# KD055HDFIA001-C001A-_5_5_Inch_MIPI_Radxa.net
KiCad netlist of a schematic drawn in EAGLE
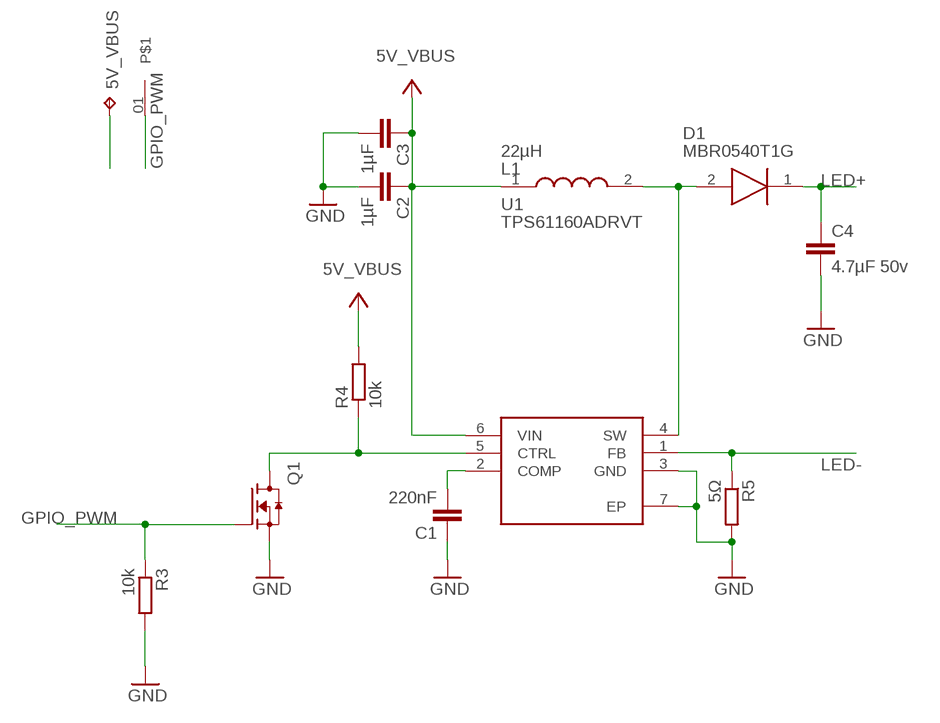
[diagram p0: schematic, sheet 1]
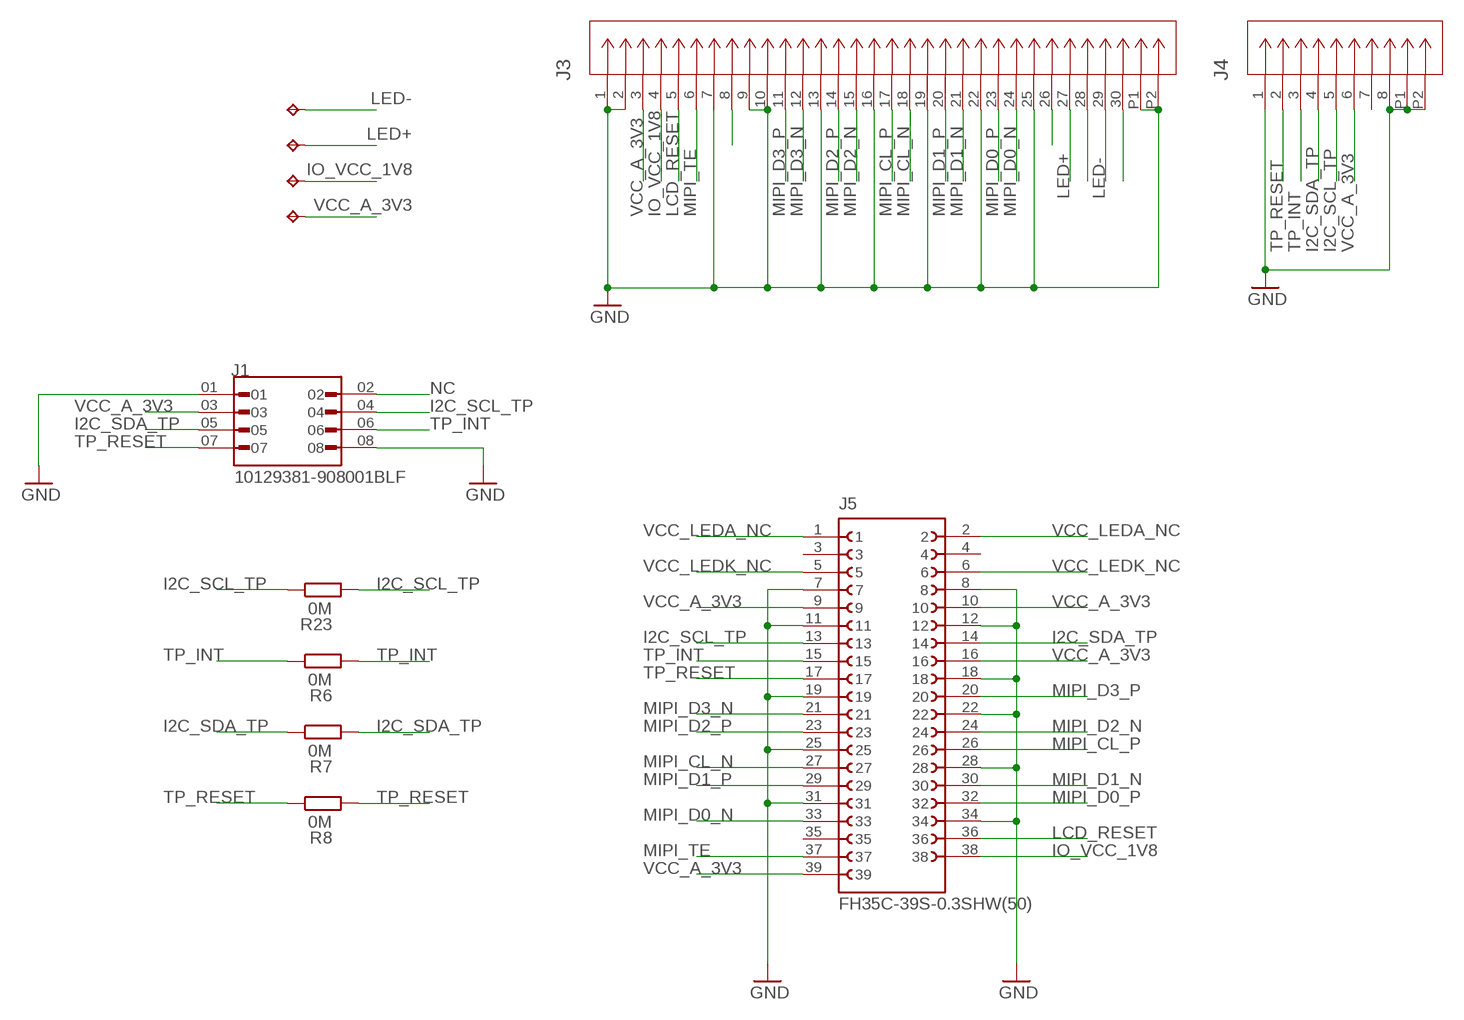
[diagram p1: schematic, sheet 2]
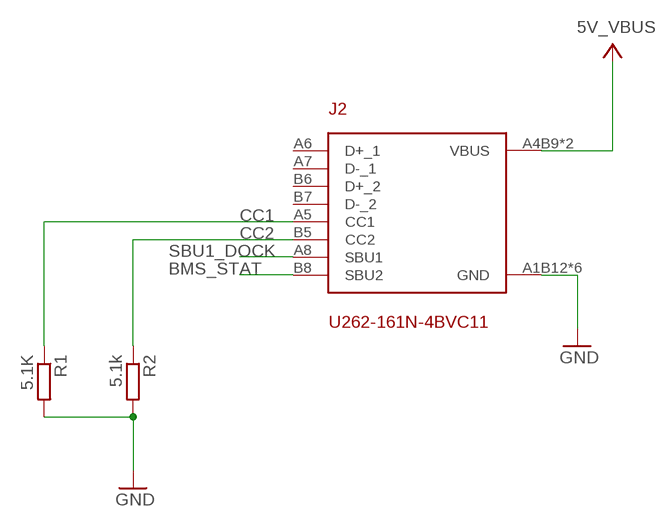
[diagram p2: schematic, sheet 3]

(export (version "E")
  (design (tool "Eeschema 10.0.6"))
  (components
    (comp (ref "5V_VBUS")
      (value "TPTP19R")
      (footprint "eagle-import:TP19R")
      (libsource (lib "eagle-import") (part "TPTP19R"))
    )
    (comp (ref "C1")
      (value "220nF")
      (footprint "eagle-import:C0603")
      (libsource (lib "eagle-import") (part "C-EUC0603"))
    )
    (comp (ref "C2")
      (value "1µF")
      (footprint "eagle-import:C0603")
      (libsource (lib "eagle-import") (part "C-EUC0603"))
    )
    (comp (ref "C3")
      (value "1µF")
      (footprint "eagle-import:C0603")
      (libsource (lib "eagle-import") (part "C-EUC0603"))
    )
    (comp (ref "C4")
      (value "4.7µF 50v")
      (footprint "eagle-import:C0805")
      (libsource (lib "eagle-import") (part "C-EUC0805"))
    )
    (comp (ref "D1")
      (value "MBR0540T1G")
      (footprint "eagle-import:SOD3716X135N")
      (fields (field (name "MOUSER_PART_NUMBER") "863-MBR0540T1G") (field (name "RS_PART_NUMBER") "0463842P"))
      (libsource (lib "eagle-import") (part "MBR0540T1G"))
    )
    (comp (ref "L1")
      (value "22µH")
      (footprint "eagle-import:VLCF4020_1")
      (fields
        (field (name "MANUFACTURER_PART_NUMBER") "VLCF4020T-220MR56")
        (field (name "MOUSER_PART_NUMBER") "810-VLCF4020T220MR56")
        (field (name "RS_PART_NUMBER") "6442781")
      )
      (libsource (lib "eagle-import") (part "VLCF4020T-220MR56"))
    )
    (comp (ref "Q1")
      (value "AO3400A")
      (footprint "eagle-import:SOT95P280X125-3N")
      (fields (field (name "DIGI-KEY_PART_NUMBER") "785-1000-1-ND") (field (name "MF") "Alpha &"))
      (libsource (lib "eagle-import") (part "AO3400A"))
    )
    (comp (ref "R3")
      (value "10k")
      (footprint "eagle-import:R0603")
      (libsource (lib "eagle-import") (part "rcl_334_R-EU_R0603"))
    )
    (comp (ref "R4")
      (value "10k")
      (footprint "eagle-import:R0603")
      (libsource (lib "eagle-import") (part "rcl_334_R-EU_R0603"))
    )
    (comp (ref "R5")
      (value "5Ω")
      (footprint "eagle-import:R0603")
      (libsource (lib "eagle-import") (part "rcl_334_R-EU_R0603"))
    )
    (comp (ref "U$1")
      (value "PAD")
      (footprint "eagle-import:AMPHENOL_10129381-908001BLF")
      (libsource (lib "eagle-import") (part "PAD"))
    )
    (comp (ref "U1")
      (value "TPS61160ADRVT")
      (footprint "eagle-import:SON65P200X200X80-7N")
      (fields
        (field (name "MOUSER_PART_NUMBER") "595-TPS61160ADRVT")
        (field (name "RS_PART_NUMBER") "7099044P")
      )
      (libsource (lib "eagle-import") (part "TPS61160ADRVT"))
    )
    (comp (ref "J2")
      (value "U262-161N-4BVC11")
      (footprint "eagle-import:U262-161N-4BVC11")
      (libsource (lib "eagle-import") (part "U262-161N-4BVC11"))
    )
    (comp (ref "R1")
      (value "5.1K")
      (footprint "eagle-import:R0603")
      (libsource (lib "eagle-import") (part "rcl_334_R-EU_R0603"))
    )
    (comp (ref "R2")
      (value "5.1k")
      (footprint "eagle-import:R0603")
      (libsource (lib "eagle-import") (part "rcl_334_R-EU_R0603"))
    )
    (comp (ref "IO_VCC_1V8")
      (value "TPTP19R")
      (footprint "eagle-import:TP19R")
      (libsource (lib "eagle-import") (part "TPTP19R"))
    )
    (comp (ref "J1")
      (value "10129381-908001BLF")
      (footprint "eagle-import:AMPHENOL_10129381-908001BLF")
      (fields (field (name "MANUFACTURER") "Amphenol ICC"))
      (libsource (lib "eagle-import") (part "10129381-908001BLF"))
    )
    (comp (ref "J3")
      (value "5051103091")
      (footprint "eagle-import:CON_5051103091_MOL")
      (fields (field (name "COPYRIGHT") "Copyright (C) 2023 Ultra Librarian. All rights reserved."))
      (libsource (lib "eagle-import") (part "5051103091"))
    )
    (comp (ref "J4")
      (value "5051100892")
      (footprint "eagle-import:CON_5051100892_MOL")
      (fields (field (name "COPYRIGHT") "Copyright (C) 2023 Ultra Librarian. All rights reserved."))
      (libsource (lib "eagle-import") (part "5051100892"))
    )
    (comp (ref "J5")
      (value "FH35C-39S-0.3SHW(50)")
      (footprint "eagle-import:HRS_FH35C-39S-0.3SHW(50)")
      (fields (field (name "MF") "Hirose Electric"))
      (libsource (lib "eagle-import") (part "FH35C-39S-0.3SHW(50)"))
    )
    (comp (ref "LED+")
      (value "TPTP19R")
      (footprint "eagle-import:TP19R")
      (libsource (lib "eagle-import") (part "TPTP19R"))
    )
    (comp (ref "LED-")
      (value "TPTP19R")
      (footprint "eagle-import:TP19R")
      (libsource (lib "eagle-import") (part "TPTP19R"))
    )
    (comp (ref "R6")
      (value "0M")
      (footprint "eagle-import:R0402")
      (libsource (lib "eagle-import") (part "R-EU_R0402"))
    )
    (comp (ref "R7")
      (value "0M")
      (footprint "eagle-import:R0402")
      (libsource (lib "eagle-import") (part "R-EU_R0402"))
    )
    (comp (ref "R8")
      (value "0M")
      (footprint "eagle-import:R0402")
      (libsource (lib "eagle-import") (part "R-EU_R0402"))
    )
    (comp (ref "R23")
      (value "0M")
      (footprint "eagle-import:R0402")
      (libsource (lib "eagle-import") (part "R-EU_R0402"))
    )
    (comp (ref "VCC_A_3V3")
      (value "TPTP19R")
      (footprint "eagle-import:TP19R")
      (libsource (lib "eagle-import") (part "TPTP19R"))
    )
  )
  (nets
    (net (code "1") (name "5V_VBUS") (class "Default")
      (node (ref "5V_VBUS") (pin "TP") (pinfunction "TP_TP") (pintype "input"))
      (node (ref "C2") (pin "1") (pinfunction "1_1") (pintype "passive"))
      (node (ref "C3") (pin "1") (pinfunction "1_1") (pintype "passive"))
      (node (ref "J2") (pin "A4B9") (pinfunction "VBUS_A4B9") (pintype "bidirectional"))
      (node (ref "J2") (pin "B4A9") (pinfunction "VBUS_B4A9") (pintype "bidirectional"))
      (node (ref "L1") (pin "1") (pinfunction "1_1") (pintype "bidirectional"))
      (node (ref "R4") (pin "2") (pinfunction "2_2") (pintype "passive"))
      (node (ref "U1") (pin "6") (pinfunction "VIN_6") (pintype "input"))
    )
    (net (code "2") (name "BMS_STAT") (class "Default")
      (node (ref "J2") (pin "B8") (pinfunction "SBU2_B8") (pintype "bidirectional"))
    )
    (net (code "3") (name "CC1") (class "Default")
      (node (ref "J2") (pin "A5") (pinfunction "CC1_A5") (pintype "bidirectional"))
      (node (ref "R1") (pin "1") (pinfunction "1_1") (pintype "passive"))
    )
    (net (code "4") (name "CC2") (class "Default")
      (node (ref "J2") (pin "B5") (pinfunction "CC2_B5") (pintype "bidirectional"))
      (node (ref "R2") (pin "1") (pinfunction "1_1") (pintype "passive"))
    )
    (net (code "5") (name "GND") (class "Default")
      (node (ref "C1") (pin "1") (pinfunction "1_1") (pintype "passive"))
      (node (ref "C2") (pin "2") (pinfunction "2_2") (pintype "passive"))
      (node (ref "C3") (pin "2") (pinfunction "2_2") (pintype "passive"))
      (node (ref "C4") (pin "2") (pinfunction "2_2") (pintype "passive"))
      (node (ref "J1") (pin "01") (pinfunction "01_01") (pintype "passive"))
      (node (ref "J1") (pin "08") (pinfunction "08_08") (pintype "passive"))
      (node (ref "J2") (pin "A1B12") (pinfunction "GND_A1B12") (pintype "bidirectional"))
      (node (ref "J2") (pin "B1A12") (pinfunction "GND_B1A12") (pintype "bidirectional"))
      (node (ref "J2") (pin "SHIELD_1") (pinfunction "GND_SHIELD_1") (pintype "bidirectional"))
      (node (ref "J2") (pin "SHIELD_2") (pinfunction "GND_SHIELD_2") (pintype "bidirectional"))
      (node (ref "J2") (pin "SHIELD_3") (pinfunction "GND_SHIELD_3") (pintype "bidirectional"))
      (node (ref "J2") (pin "SHIELD_4") (pinfunction "GND_SHIELD_4") (pintype "bidirectional"))
      (node (ref "J3") (pin "1") (pinfunction "1_1") (pintype "passive"))
      (node (ref "J3") (pin "10") (pinfunction "10_10") (pintype "passive"))
      (node (ref "J3") (pin "13") (pinfunction "13_13") (pintype "passive"))
      (node (ref "J3") (pin "16") (pinfunction "16_16") (pintype "passive"))
      (node (ref "J3") (pin "19") (pinfunction "19_19") (pintype "passive"))
      (node (ref "J3") (pin "2") (pinfunction "2_2") (pintype "passive"))
      (node (ref "J3") (pin "22") (pinfunction "22_22") (pintype "passive"))
      (node (ref "J3") (pin "25") (pinfunction "25_25") (pintype "passive"))
      (node (ref "J3") (pin "7") (pinfunction "7_7") (pintype "passive"))
      (node (ref "J3") (pin "9") (pinfunction "9_9") (pintype "passive"))
      (node (ref "J3") (pin "P1") (pinfunction "P1_P1") (pintype "passive"))
      (node (ref "J3") (pin "P2") (pinfunction "P2_P2") (pintype "passive"))
      (node (ref "J4") (pin "1") (pinfunction "1_1") (pintype "passive"))
      (node (ref "J4") (pin "8") (pinfunction "8_8") (pintype "passive"))
      (node (ref "J4") (pin "P1") (pinfunction "P1_P1") (pintype "passive"))
      (node (ref "J4") (pin "P2") (pinfunction "P2_P2") (pintype "passive"))
      (node (ref "J5") (pin "11") (pinfunction "11_11") (pintype "passive"))
      (node (ref "J5") (pin "12") (pinfunction "12_12") (pintype "passive"))
      (node (ref "J5") (pin "18") (pinfunction "18_18") (pintype "passive"))
      (node (ref "J5") (pin "19") (pinfunction "19_19") (pintype "passive"))
      (node (ref "J5") (pin "22") (pinfunction "22_22") (pintype "passive"))
      (node (ref "J5") (pin "25") (pinfunction "25_25") (pintype "passive"))
      (node (ref "J5") (pin "28") (pinfunction "28_28") (pintype "passive"))
      (node (ref "J5") (pin "31") (pinfunction "31_31") (pintype "passive"))
      (node (ref "J5") (pin "34") (pinfunction "34_34") (pintype "passive"))
      (node (ref "J5") (pin "7") (pinfunction "7_7") (pintype "passive"))
      (node (ref "J5") (pin "8") (pinfunction "8_8") (pintype "passive"))
      (node (ref "Q1") (pin "2") (pinfunction "S_2") (pintype "passive"))
      (node (ref "R1") (pin "2") (pinfunction "2_2") (pintype "passive"))
      (node (ref "R2") (pin "2") (pinfunction "2_2") (pintype "passive"))
      (node (ref "R3") (pin "2") (pinfunction "2_2") (pintype "passive"))
      (node (ref "R5") (pin "2") (pinfunction "2_2") (pintype "passive"))
      (node (ref "U1") (pin "3") (pinfunction "GND_3") (pintype "output"))
      (node (ref "U1") (pin "7") (pinfunction "EP_7") (pintype "power_in"))
    )
    (net (code "6") (name "GPIO_PWM") (class "Default")
      (node (ref "Q1") (pin "1") (pinfunction "G_1") (pintype "passive"))
      (node (ref "R3") (pin "1") (pinfunction "1_1") (pintype "passive"))
      (node (ref "U$1") (pin "01") (pinfunction "P$1_01") (pintype "bidirectional"))
    )
    (net (code "7") (name "I2C_SCL_TP") (class "Default")
      (node (ref "J1") (pin "04") (pinfunction "04_04") (pintype "passive"))
      (node (ref "J4") (pin "5") (pinfunction "5_5") (pintype "passive"))
      (node (ref "J5") (pin "13") (pinfunction "13_13") (pintype "passive"))
      (node (ref "R23") (pin "1") (pinfunction "1_1") (pintype "passive"))
      (node (ref "R23") (pin "2") (pinfunction "2_2") (pintype "passive"))
    )
    (net (code "8") (name "I2C_SDA_TP") (class "Default")
      (node (ref "J1") (pin "05") (pinfunction "05_05") (pintype "passive"))
      (node (ref "J4") (pin "4") (pinfunction "4_4") (pintype "passive"))
      (node (ref "J5") (pin "14") (pinfunction "14_14") (pintype "passive"))
      (node (ref "R7") (pin "1") (pinfunction "1_1") (pintype "passive"))
      (node (ref "R7") (pin "2") (pinfunction "2_2") (pintype "passive"))
    )
    (net (code "9") (name "IO_VCC_1V8") (class "Default")
      (node (ref "IO_VCC_1V8") (pin "TP") (pinfunction "TP_TP") (pintype "input"))
      (node (ref "J3") (pin "4") (pinfunction "4_4") (pintype "passive"))
      (node (ref "J5") (pin "38") (pinfunction "38_38") (pintype "passive"))
    )
    (net (code "10") (name "LCD_RESET") (class "Default")
      (node (ref "J3") (pin "5") (pinfunction "5_5") (pintype "passive"))
      (node (ref "J5") (pin "36") (pinfunction "36_36") (pintype "passive"))
    )
    (net (code "11") (name "LED+") (class "Default")
      (node (ref "C4") (pin "1") (pinfunction "1_1") (pintype "passive"))
      (node (ref "D1") (pin "1") (pinfunction "K_1") (pintype "bidirectional"))
      (node (ref "J3") (pin "27") (pinfunction "27_27") (pintype "passive"))
      (node (ref "LED+") (pin "TP") (pinfunction "TP_TP") (pintype "input"))
    )
    (net (code "12") (name "LED-") (class "Default")
      (node (ref "J3") (pin "29") (pinfunction "29_29") (pintype "passive"))
      (node (ref "LED-") (pin "TP") (pinfunction "TP_TP") (pintype "input"))
      (node (ref "R5") (pin "1") (pinfunction "1_1") (pintype "passive"))
      (node (ref "U1") (pin "1") (pinfunction "FB_1") (pintype "input"))
    )
    (net (code "13") (name "MIPI_CL_N") (class "Default")
      (node (ref "J3") (pin "18") (pinfunction "18_18") (pintype "passive"))
      (node (ref "J5") (pin "27") (pinfunction "27_27") (pintype "passive"))
    )
    (net (code "14") (name "MIPI_CL_P") (class "Default")
      (node (ref "J3") (pin "17") (pinfunction "17_17") (pintype "passive"))
      (node (ref "J5") (pin "26") (pinfunction "26_26") (pintype "passive"))
    )
    (net (code "15") (name "MIPI_D0_N") (class "Default")
      (node (ref "J3") (pin "24") (pinfunction "24_24") (pintype "passive"))
      (node (ref "J5") (pin "33") (pinfunction "33_33") (pintype "passive"))
    )
    (net (code "16") (name "MIPI_D0_P") (class "Default")
      (node (ref "J3") (pin "23") (pinfunction "23_23") (pintype "passive"))
      (node (ref "J5") (pin "32") (pinfunction "32_32") (pintype "passive"))
    )
    (net (code "17") (name "MIPI_D1_N") (class "Default")
      (node (ref "J3") (pin "21") (pinfunction "21_21") (pintype "passive"))
      (node (ref "J5") (pin "30") (pinfunction "30_30") (pintype "passive"))
    )
    (net (code "18") (name "MIPI_D1_P") (class "Default")
      (node (ref "J3") (pin "20") (pinfunction "20_20") (pintype "passive"))
      (node (ref "J5") (pin "29") (pinfunction "29_29") (pintype "passive"))
    )
    (net (code "19") (name "MIPI_D2_N") (class "Default")
      (node (ref "J3") (pin "15") (pinfunction "15_15") (pintype "passive"))
      (node (ref "J5") (pin "24") (pinfunction "24_24") (pintype "passive"))
    )
    (net (code "20") (name "MIPI_D2_P") (class "Default")
      (node (ref "J3") (pin "14") (pinfunction "14_14") (pintype "passive"))
      (node (ref "J5") (pin "23") (pinfunction "23_23") (pintype "passive"))
    )
    (net (code "21") (name "MIPI_D3_N") (class "Default")
      (node (ref "J3") (pin "12") (pinfunction "12_12") (pintype "passive"))
      (node (ref "J5") (pin "21") (pinfunction "21_21") (pintype "passive"))
    )
    (net (code "22") (name "MIPI_D3_P") (class "Default")
      (node (ref "J3") (pin "11") (pinfunction "11_11") (pintype "passive"))
      (node (ref "J5") (pin "20") (pinfunction "20_20") (pintype "passive"))
    )
    (net (code "23") (name "MIPI_TE") (class "Default")
      (node (ref "J3") (pin "6") (pinfunction "6_6") (pintype "passive"))
      (node (ref "J5") (pin "37") (pinfunction "37_37") (pintype "passive"))
    )
    (net (code "24") (name "NC") (class "Default")
      (node (ref "J1") (pin "02") (pinfunction "02_02") (pintype "passive"))
    )
    (net (code "25") (name "Net-(D1-A)") (class "Default")
      (node (ref "D1") (pin "2") (pinfunction "A_2") (pintype "bidirectional"))
      (node (ref "L1") (pin "2") (pinfunction "2_2") (pintype "bidirectional"))
      (node (ref "U1") (pin "4") (pinfunction "SW_4") (pintype "input"))
    )
    (net (code "26") (name "Net-(Q1-D)") (class "Default")
      (node (ref "Q1") (pin "3") (pinfunction "D_3") (pintype "passive"))
      (node (ref "R4") (pin "1") (pinfunction "1_1") (pintype "passive"))
      (node (ref "U1") (pin "5") (pinfunction "CTRL_5") (pintype "input"))
    )
    (net (code "27") (name "Net-(U1-COMP)") (class "Default")
      (node (ref "C1") (pin "2") (pinfunction "2_2") (pintype "passive"))
      (node (ref "U1") (pin "2") (pinfunction "COMP_2") (pintype "output"))
    )
    (net (code "28") (name "SBU1_DOCK") (class "Default")
      (node (ref "J2") (pin "A8") (pinfunction "SBU1_A8") (pintype "bidirectional"))
    )
    (net (code "29") (name "TP_INT") (class "Default")
      (node (ref "J1") (pin "06") (pinfunction "06_06") (pintype "passive"))
      (node (ref "J4") (pin "3") (pinfunction "3_3") (pintype "passive"))
      (node (ref "J5") (pin "15") (pinfunction "15_15") (pintype "passive"))
      (node (ref "R6") (pin "1") (pinfunction "1_1") (pintype "passive"))
      (node (ref "R6") (pin "2") (pinfunction "2_2") (pintype "passive"))
    )
    (net (code "30") (name "TP_RESET") (class "Default")
      (node (ref "J1") (pin "07") (pinfunction "07_07") (pintype "passive"))
      (node (ref "J4") (pin "2") (pinfunction "2_2") (pintype "passive"))
      (node (ref "J5") (pin "17") (pinfunction "17_17") (pintype "passive"))
      (node (ref "R8") (pin "1") (pinfunction "1_1") (pintype "passive"))
      (node (ref "R8") (pin "2") (pinfunction "2_2") (pintype "passive"))
    )
    (net (code "31") (name "VCC_A_3V3") (class "Default")
      (node (ref "J1") (pin "03") (pinfunction "03_03") (pintype "passive"))
      (node (ref "J3") (pin "3") (pinfunction "3_3") (pintype "passive"))
      (node (ref "J4") (pin "6") (pinfunction "6_6") (pintype "passive"))
      (node (ref "J5") (pin "10") (pinfunction "10_10") (pintype "passive"))
      (node (ref "J5") (pin "16") (pinfunction "16_16") (pintype "passive"))
      (node (ref "J5") (pin "39") (pinfunction "39_39") (pintype "passive"))
      (node (ref "J5") (pin "9") (pinfunction "9_9") (pintype "passive"))
      (node (ref "VCC_A_3V3") (pin "TP") (pinfunction "TP_TP") (pintype "input"))
    )
    (net (code "32") (name "VCC_LEDA_NC") (class "Default")
      (node (ref "J5") (pin "1") (pinfunction "1_1") (pintype "passive"))
      (node (ref "J5") (pin "2") (pinfunction "2_2") (pintype "passive"))
    )
    (net (code "33") (name "VCC_LEDK_NC") (class "Default")
      (node (ref "J5") (pin "5") (pinfunction "5_5") (pintype "passive"))
      (node (ref "J5") (pin "6") (pinfunction "6_6") (pintype "passive"))
    )
    (net (code "34") (name "unconnected-(J2-D+_1-PadA6)") (class "Default")
      (node (ref "J2") (pin "A6") (pinfunction "D+_1_A6") (pintype "bidirectional"))
    )
    (net (code "35") (name "unconnected-(J2-D+_2-PadB6)") (class "Default")
      (node (ref "J2") (pin "B6") (pinfunction "D+_2_B6") (pintype "bidirectional"))
    )
    (net (code "36") (name "unconnected-(J2-D-_1-PadA7)") (class "Default")
      (node (ref "J2") (pin "A7") (pinfunction "D-_1_A7") (pintype "bidirectional"))
    )
    (net (code "37") (name "unconnected-(J2-D-_2-PadB7)") (class "Default")
      (node (ref "J2") (pin "B7") (pinfunction "D-_2_B7") (pintype "bidirectional"))
    )
    (net (code "38") (name "unconnected-(J3-Pad8)") (class "Default")
      (node (ref "J3") (pin "8") (pinfunction "8_8") (pintype "passive"))
    )
    (net (code "39") (name "unconnected-(J3-Pad26)") (class "Default")
      (node (ref "J3") (pin "26") (pinfunction "26_26") (pintype "passive"))
    )
    (net (code "40") (name "unconnected-(J3-Pad28)") (class "Default")
      (node (ref "J3") (pin "28") (pinfunction "28_28") (pintype "passive"))
    )
    (net (code "41") (name "unconnected-(J3-Pad30)") (class "Default")
      (node (ref "J3") (pin "30") (pinfunction "30_30") (pintype "passive"))
    )
    (net (code "42") (name "unconnected-(J4-Pad7)") (class "Default")
      (node (ref "J4") (pin "7") (pinfunction "7_7") (pintype "passive"))
    )
    (net (code "43") (name "unconnected-(J5-Pad3)") (class "Default")
      (node (ref "J5") (pin "3") (pinfunction "3_3") (pintype "passive"))
    )
    (net (code "44") (name "unconnected-(J5-Pad4)") (class "Default")
      (node (ref "J5") (pin "4") (pinfunction "4_4") (pintype "passive"))
    )
    (net (code "45") (name "unconnected-(J5-Pad35)") (class "Default")
      (node (ref "J5") (pin "35") (pinfunction "35_35") (pintype "passive"))
    )
  )
)
